# Memory.net
KiCad netlist of a schematic drawn in Altium Designer
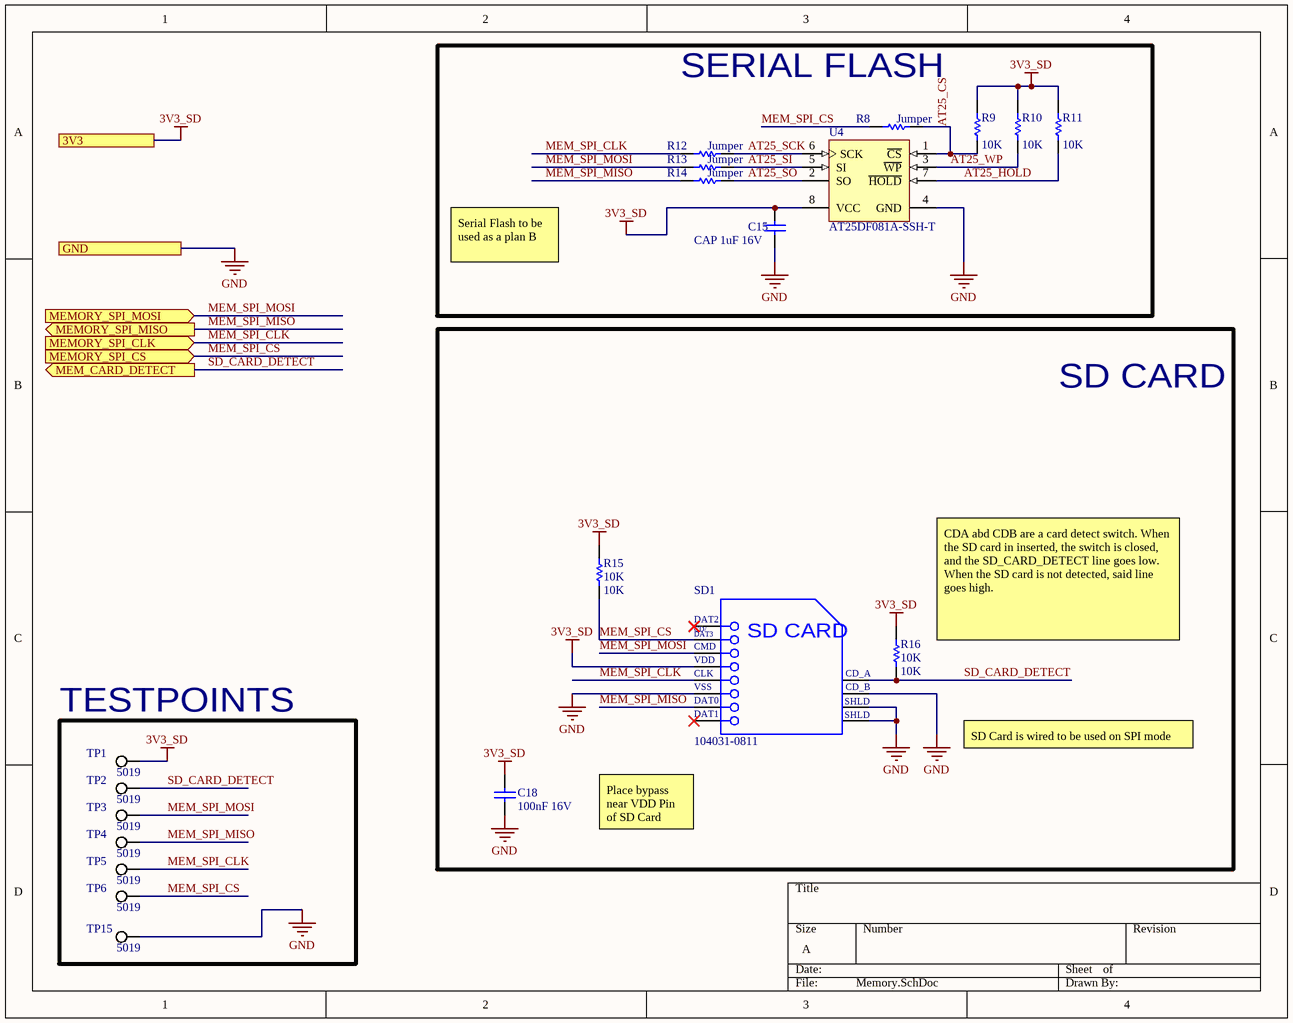
[diagram p0: Memory.SchDoc]

(export (version "E")
  (design (tool "Eeschema 10.0.6"))
  (components
    (comp (ref "C15")
      (value "CAP 1uF 16V")
      (footprint "CAPC0603(1608)100_N")
      (description "CAP 1uF 16V ±10% 0603 (1608 Metric) Thickness 1mm SMD")
      (fields (field (name "TOLERANCE") "Â±10%"))
      (libsource (lib "Altium Content Vault") (part "CAP"))
    )
    (comp (ref "C18")
      (value "100nF 16V")
      (footprint "CAPC0603(1608)100_N")
      (description "CAP 100nF 16V ±10% 0603 (1608 Metric) Thickness 1mm SMD")
      (fields (field (name "TOLERANCE") "Â±10%"))
      (libsource (lib "Altium Content Vault") (part "CAP"))
    )
    (comp (ref "R8")
      (value "Jumper")
      (footprint "RESC0603(1608)_N")
      (description "Jumper 0603 (1608 Metric)")
      (fields (field (name "POWER") "None"))
      (libsource (lib "Altium Content Vault") (part "RES"))
    )
    (comp (ref "R9")
      (value "10K")
      (footprint "J1-0603")
      (description "Resistor")
      (fields (field (name "PUBLISHER") "Altium Limited"))
      (libsource (lib "Miscellaneous Devices") (part "Res1"))
    )
    (comp (ref "R10")
      (value "10K")
      (footprint "J1-0603")
      (description "Resistor")
      (fields (field (name "PUBLISHER") "Altium Limited"))
      (libsource (lib "Miscellaneous Devices") (part "Res1"))
    )
    (comp (ref "R11")
      (value "10K")
      (footprint "J1-0603")
      (description "Resistor")
      (fields (field (name "PUBLISHER") "Altium Limited"))
      (libsource (lib "Miscellaneous Devices") (part "Res1"))
    )
    (comp (ref "R12")
      (value "Jumper")
      (footprint "RESC0603(1608)_N")
      (description "Jumper 0603 (1608 Metric)")
      (fields (field (name "POWER") "None"))
      (libsource (lib "Altium Content Vault") (part "RES"))
    )
    (comp (ref "R13")
      (value "Jumper")
      (footprint "RESC0603(1608)_N")
      (description "Jumper 0603 (1608 Metric)")
      (fields (field (name "POWER") "None"))
      (libsource (lib "Altium Content Vault") (part "RES"))
    )
    (comp (ref "R14")
      (value "Jumper")
      (footprint "RESC0603(1608)_N")
      (description "Jumper 0603 (1608 Metric)")
      (fields (field (name "POWER") "None"))
      (libsource (lib "Altium Content Vault") (part "RES"))
    )
    (comp (ref "R15")
      (value "10K")
      (footprint "J1-0603")
      (description "Resistor")
      (fields (field (name "ALTIUM_VALUE") "10K") (field (name "PUBLISHER") "Altium Limited"))
      (libsource (lib "Miscellaneous Devices") (part "Res1"))
    )
    (comp (ref "R16")
      (value "10K")
      (footprint "J1-0603")
      (description "Resistor")
      (fields (field (name "ALTIUM_VALUE") "10K") (field (name "PUBLISHER") "Altium Limited"))
      (libsource (lib "Miscellaneous Devices") (part "Res1"))
    )
    (comp (ref "SD1")
      (value "104031-0811")
      (footprint "MOLX-104031-0811_V")
      (description "Micro SD Card, RA, -25 to 85 degC, 8-Pin SMD, RoHS, Tape and Reel")
      (fields (field (name "MANUFACTURER") "Molex"))
      (libsource (lib "Altium Content Vault") (part "CN-SD-8-2SW-2S"))
    )
    (comp (ref "TP1")
      (value "5019")
      (footprint "KSTN-5019_V")
      (description "Test Point, 1 Position SMD, RoHS, Tape and Reel")
      (libsource (lib "Altium Content Vault") (part "TESTPOINT_WHITE"))
    )
    (comp (ref "TP2")
      (value "5019")
      (footprint "KSTN-5019_V")
      (description "Test Point, 1 Position SMD, RoHS, Tape and Reel")
      (libsource (lib "Altium Content Vault") (part "TESTPOINT_WHITE"))
    )
    (comp (ref "TP3")
      (value "5019")
      (footprint "KSTN-5019_V")
      (description "Test Point, 1 Position SMD, RoHS, Tape and Reel")
      (libsource (lib "Altium Content Vault") (part "TESTPOINT_WHITE"))
    )
    (comp (ref "TP4")
      (value "5019")
      (footprint "KSTN-5019_V")
      (description "Test Point, 1 Position SMD, RoHS, Tape and Reel")
      (libsource (lib "Altium Content Vault") (part "TESTPOINT_WHITE"))
    )
    (comp (ref "TP5")
      (value "5019")
      (footprint "KSTN-5019_V")
      (description "Test Point, 1 Position SMD, RoHS, Tape and Reel")
      (libsource (lib "Altium Content Vault") (part "TESTPOINT_WHITE"))
    )
    (comp (ref "TP6")
      (value "5019")
      (footprint "KSTN-5019_V")
      (description "Test Point, 1 Position SMD, RoHS, Tape and Reel")
      (libsource (lib "Altium Content Vault") (part "TESTPOINT_WHITE"))
    )
    (comp (ref "TP15")
      (value "5019")
      (footprint "KSTN-5019_V")
      (description "Test Point, 1 Position SMD, RoHS, Tape and Reel")
      (libsource (lib "Altium Content Vault") (part "TESTPOINT_WHITE"))
    )
    (comp (ref "U4")
      (value "AT25DF081A-SSH-T")
      (footprint "AT25DF081A-SSH-T")
      (description "IC FLASH 8MBIT 100MHZ 8SOIC")
      (fields (field (name "MANUFACTURER") "Adesto Technologies"))
      (libsource (lib "Schematics") (part "AT25DF081A-SSH-T"))
    )
  )
  (nets
    (net (code "1") (name "/AT25_CS") (class "Default")
      (node (ref "R8") (pin "2") (pinfunction "2_2") (pintype "passive"))
      (node (ref "R9") (pin "1") (pinfunction "1_1") (pintype "passive"))
      (node (ref "U4") (pin "1") (pinfunction "~{CS}_1") (pintype "input"))
    )
    (net (code "2") (name "/AT25_HOLD") (class "Default")
      (node (ref "R11") (pin "1") (pinfunction "1_1") (pintype "passive"))
      (node (ref "U4") (pin "7") (pinfunction "~{HOLD}_7") (pintype "input"))
    )
    (net (code "3") (name "/AT25_SCK") (class "Default")
      (node (ref "R12") (pin "2") (pinfunction "2_2") (pintype "passive"))
      (node (ref "U4") (pin "6") (pinfunction "SCK_6") (pintype "input"))
    )
    (net (code "4") (name "/AT25_SI") (class "Default")
      (node (ref "R13") (pin "2") (pinfunction "2_2") (pintype "passive"))
      (node (ref "U4") (pin "5") (pinfunction "SI_5") (pintype "input"))
    )
    (net (code "5") (name "/AT25_SO") (class "Default")
      (node (ref "R14") (pin "2") (pinfunction "2_2") (pintype "passive"))
      (node (ref "U4") (pin "2") (pinfunction "SO_2") (pintype "tri_state"))
    )
    (net (code "6") (name "/AT25_WP") (class "Default")
      (node (ref "R10") (pin "1") (pinfunction "1_1") (pintype "passive"))
      (node (ref "U4") (pin "3") (pinfunction "~{WP}_3") (pintype "input"))
    )
    (net (code "7") (name "/MEM_SPI_CLK") (class "Default")
      (node (ref "R12") (pin "1") (pinfunction "1_1") (pintype "passive"))
      (node (ref "SD1") (pin "5") (pinfunction "CLK_5") (pintype "passive"))
      (node (ref "TP5") (pin "1") (pinfunction "1_1") (pintype "passive"))
    )
    (net (code "8") (name "/MEM_SPI_CS") (class "Default")
      (node (ref "R15") (pin "1") (pinfunction "1_1") (pintype "passive"))
      (node (ref "R8") (pin "1") (pinfunction "1_1") (pintype "passive"))
      (node (ref "SD1") (pin "2") (pinfunction "CMD_2") (pintype "passive"))
      (node (ref "TP6") (pin "1") (pinfunction "1_1") (pintype "passive"))
    )
    (net (code "9") (name "/MEM_SPI_MISO") (class "Default")
      (node (ref "R14") (pin "1") (pinfunction "1_1") (pintype "passive"))
      (node (ref "SD1") (pin "7") (pinfunction "DAT0_7") (pintype "passive"))
      (node (ref "TP4") (pin "1") (pinfunction "1_1") (pintype "passive"))
    )
    (net (code "10") (name "/MEM_SPI_MOSI") (class "Default")
      (node (ref "R13") (pin "1") (pinfunction "1_1") (pintype "passive"))
      (node (ref "SD1") (pin "3") (pinfunction "VSS1_3") (pintype "passive"))
      (node (ref "TP3") (pin "1") (pinfunction "1_1") (pintype "passive"))
    )
    (net (code "11") (name "/SD_CARD_DETECT") (class "Default")
      (node (ref "R16") (pin "1") (pinfunction "1_1") (pintype "passive"))
      (node (ref "SD1") (pin "9") (pinfunction "CD_A_9") (pintype "passive"))
      (node (ref "TP2") (pin "1") (pinfunction "1_1") (pintype "passive"))
    )
    (net (code "12") (name "3V3_SD") (class "Default")
      (node (ref "C15") (pin "2") (pinfunction "2_2") (pintype "passive"))
      (node (ref "C18") (pin "2") (pinfunction "2_2") (pintype "passive"))
      (node (ref "R10") (pin "2") (pinfunction "2_2") (pintype "passive"))
      (node (ref "R11") (pin "2") (pinfunction "2_2") (pintype "passive"))
      (node (ref "R15") (pin "2") (pinfunction "2_2") (pintype "passive"))
      (node (ref "R16") (pin "2") (pinfunction "2_2") (pintype "passive"))
      (node (ref "R9") (pin "2") (pinfunction "2_2") (pintype "passive"))
      (node (ref "SD1") (pin "4") (pinfunction "VDD_4") (pintype "passive"))
      (node (ref "TP1") (pin "1") (pinfunction "1_1") (pintype "passive"))
      (node (ref "U4") (pin "8") (pinfunction "VCC_8") (pintype "power_in"))
    )
    (net (code "13") (name "GND") (class "Default")
      (node (ref "C15") (pin "1") (pinfunction "1_1") (pintype "passive"))
      (node (ref "C18") (pin "1") (pinfunction "1_1") (pintype "passive"))
      (node (ref "SD1") (pin "10") (pinfunction "CD_B_10") (pintype "passive"))
      (node (ref "SD1") (pin "11") (pinfunction "SHLD1_11") (pintype "passive"))
      (node (ref "SD1") (pin "12") (pinfunction "SHLD2_12") (pintype "passive"))
      (node (ref "SD1") (pin "6") (pinfunction "VSS2_6") (pintype "passive"))
      (node (ref "TP15") (pin "1") (pinfunction "1_1") (pintype "passive"))
      (node (ref "U4") (pin "4") (pinfunction "GND_4") (pintype "power_in"))
    )
    (net (code "14") (name "unconnected-(SD1-CD{slash}DAT3-Pad1)") (class "Default")
      (node (ref "SD1") (pin "1") (pinfunction "CD/DAT3_1") (pintype "passive+no_connect"))
    )
    (net (code "15") (name "unconnected-(SD1-DAT1-Pad8)") (class "Default")
      (node (ref "SD1") (pin "8") (pinfunction "DAT1_8") (pintype "passive+no_connect"))
    )
  )
)
